# door_lock_2.net
KiCad netlist of a schematic drawn in EAGLE
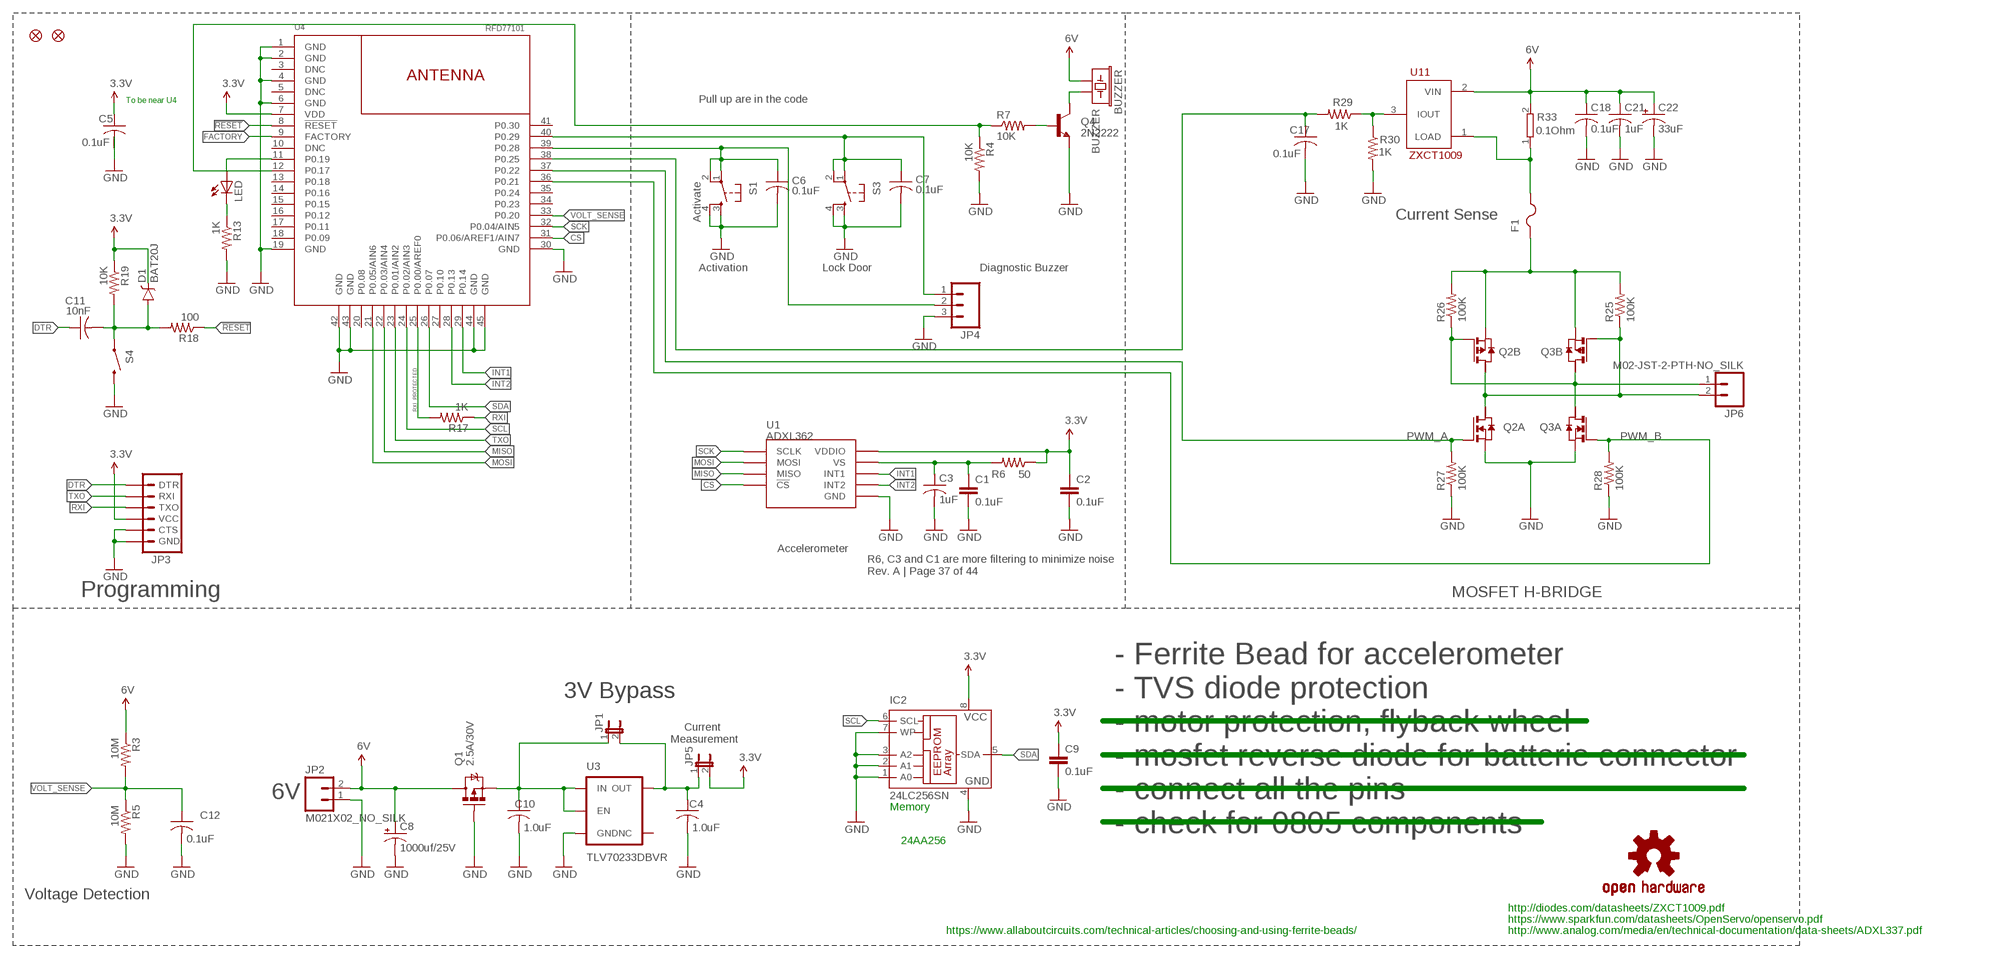
[diagram p0: schematic, sheet 1]

(export (version "E")
  (design (tool "Eeschema 10.0.6"))
  (components
    (comp (ref "BUZZER")
      (value "BUZZER")
      (footprint "eagle-import:BUZZER-12MM-NS")
      (libsource (lib "eagle-import") (part "BUZZERNS"))
    )
    (comp (ref "C1")
      (value "0.1uF")
      (footprint "eagle-import:0805")
      (libsource (lib "eagle-import") (part "CAP0805"))
    )
    (comp (ref "C2")
      (value "0.1uF")
      (footprint "eagle-import:0805")
      (libsource (lib "eagle-import") (part "CAP0805"))
    )
    (comp (ref "C3")
      (value "1uF")
      (footprint "eagle-import:C0805")
      (libsource (lib "eagle-import") (part "C-USC0805"))
    )
    (comp (ref "C4")
      (value "1.0uF")
      (footprint "eagle-import:C0805")
      (libsource (lib "eagle-import") (part "C-USC0805"))
    )
    (comp (ref "C5")
      (value "0.1uF")
      (footprint "eagle-import:C0805")
      (libsource (lib "eagle-import") (part "C-USC0805"))
    )
    (comp (ref "C6")
      (value "0.1uF")
      (footprint "eagle-import:C0805")
      (libsource (lib "eagle-import") (part "C-USC0805"))
    )
    (comp (ref "C7")
      (value "0.1uF")
      (footprint "eagle-import:C0805")
      (libsource (lib "eagle-import") (part "C-USC0805"))
    )
    (comp (ref "C8")
      (value "1000uf/25V")
      (footprint "eagle-import:CPOL-RADIAL-1000UF-25V-KIT")
      (libsource (lib "eagle-import") (part "1000UF-25V(PTH)KIT"))
    )
    (comp (ref "C9")
      (value "0.1uF")
      (footprint "eagle-import:0805")
      (libsource (lib "eagle-import") (part "CAP0805"))
    )
    (comp (ref "C10")
      (value "1.0uF")
      (footprint "eagle-import:C0805")
      (libsource (lib "eagle-import") (part "C-USC0805"))
    )
    (comp (ref "C11")
      (value "10nF")
      (footprint "eagle-import:C0805")
      (libsource (lib "eagle-import") (part "C-USC0805"))
    )
    (comp (ref "C12")
      (value "0.1uF")
      (footprint "eagle-import:C0805")
      (libsource (lib "eagle-import") (part "C-USC0805"))
    )
    (comp (ref "C17")
      (value "0.1uF")
      (footprint "eagle-import:C0805")
      (libsource (lib "eagle-import") (part "C-USC0805"))
    )
    (comp (ref "C18")
      (value "0.1uF")
      (footprint "eagle-import:C0805")
      (libsource (lib "eagle-import") (part "C-USC0805"))
    )
    (comp (ref "C21")
      (value "1uF")
      (footprint "eagle-import:C0805")
      (libsource (lib "eagle-import") (part "C-USC0805"))
    )
    (comp (ref "C22")
      (value "33uF")
      (footprint "eagle-import:EIA3528")
      (libsource (lib "eagle-import") (part "CAP_POL3528"))
    )
    (comp (ref "D1")
      (value "BAT20J")
      (footprint "eagle-import:SOD-323")
      (libsource (lib "eagle-import") (part "DIODE-SCHOTTKY-BAT20J"))
    )
    (comp (ref "F1")
      (value "PTCFUSE-1812")
      (footprint "eagle-import:1812")
      (libsource (lib "eagle-import") (part "PTCFUSE-1812"))
    )
    (comp (ref "IC2")
      (value "24LC256SN")
      (footprint "eagle-import:SO-08")
      (fields (field (name "MF") "MICROCHIP") (field (name "MPN") "24LC256-I/SN"))
      (libsource (lib "eagle-import") (part "24SNLC256"))
    )
    (comp (ref "JP1")
      (value "JUMPER-2SMD-NO")
      (footprint "eagle-import:SJ_2S-NO")
      (libsource (lib "eagle-import") (part "SparkFun-Retired_JUMPER-2SMD-NO"))
    )
    (comp (ref "JP2")
      (value "M021X02_NO_SILK")
      (footprint "eagle-import:1X02_NO_SILK")
      (libsource (lib "eagle-import") (part "M021X02_NO_SILK"))
    )
    (comp (ref "JP3")
      (value "ARDUINO_SERIAL_PROGRAMPTH")
      (footprint "eagle-import:1X06")
      (libsource (lib "eagle-import") (part "ARDUINO_SERIAL_PROGRAMPTH"))
    )
    (comp (ref "JP4")
      (value "M03PTH")
      (footprint "eagle-import:1X03")
      (libsource (lib "eagle-import") (part "M03PTH"))
    )
    (comp (ref "JP5")
      (value "JUMPER-2PTH")
      (footprint "eagle-import:1X02")
      (libsource (lib "eagle-import") (part "JUMPER-2PTH"))
    )
    (comp (ref "JP6")
      (value "M02-JST-2-PTH-NO_SILK")
      (footprint "eagle-import:JST-2-PTH-NS")
      (libsource (lib "eagle-import") (part "M02-JST-2-PTH-NO_SILK"))
    )
    (comp (ref "JP9")
      (value "FIDUCIALUFIDUCIAL")
      (footprint "eagle-import:MICRO-FIDUCIAL")
      (libsource (lib "eagle-import") (part "FIDUCIALUFIDUCIAL"))
    )
    (comp (ref "JP10")
      (value "FIDUCIALUFIDUCIAL")
      (footprint "eagle-import:MICRO-FIDUCIAL")
      (libsource (lib "eagle-import") (part "FIDUCIALUFIDUCIAL"))
    )
    (comp (ref "LED")
      (value "LEDCHIP-LED0805")
      (footprint "eagle-import:CHIP-LED0805")
      (libsource (lib "eagle-import") (part "LEDCHIP-LED0805"))
    )
    (comp (ref "Q1")
      (value "2.5A/30V")
      (footprint "eagle-import:SOT23-3")
      (libsource (lib "eagle-import") (part "MOSFET-PCHANNELDMG2307L"))
    )
    (comp (ref "Q2")
      (value "PN_MOSFET-SO8")
      (footprint "eagle-import:SO8")
      (libsource (lib "eagle-import") (part "PN_MOSFET-SO8"))
    )
    (comp (ref "Q3")
      (value "PN_MOSFET-SO8")
      (footprint "eagle-import:SO8")
      (libsource (lib "eagle-import") (part "PN_MOSFET-SO8"))
    )
    (comp (ref "Q4")
      (value "2N2222")
      (footprint "eagle-import:SOT23")
      (libsource (lib "eagle-import") (part "TRANSISTOR_NPNSOT23"))
    )
    (comp (ref "R3")
      (value "10M")
      (footprint "eagle-import:R0805")
      (libsource (lib "eagle-import") (part "R-US_R0805"))
    )
    (comp (ref "R4")
      (value "10K")
      (footprint "eagle-import:R0805")
      (libsource (lib "eagle-import") (part "R-US_R0805"))
    )
    (comp (ref "R5")
      (value "10M")
      (footprint "eagle-import:R0805")
      (libsource (lib "eagle-import") (part "R-US_R0805"))
    )
    (comp (ref "R6")
      (value "50")
      (footprint "eagle-import:R0805")
      (libsource (lib "eagle-import") (part "R-US_R0805"))
    )
    (comp (ref "R7")
      (value "10K")
      (footprint "eagle-import:R0805")
      (libsource (lib "eagle-import") (part "R-US_R0805"))
    )
    (comp (ref "R13")
      (value "1K")
      (footprint "eagle-import:R0805")
      (libsource (lib "eagle-import") (part "R-US_R0805"))
    )
    (comp (ref "R17")
      (value "1K")
      (footprint "eagle-import:R0805")
      (libsource (lib "eagle-import") (part "R-US_R0805"))
    )
    (comp (ref "R18")
      (value "100")
      (footprint "eagle-import:R0805")
      (libsource (lib "eagle-import") (part "R-US_R0805"))
    )
    (comp (ref "R19")
      (value "10K")
      (footprint "eagle-import:R0805")
      (libsource (lib "eagle-import") (part "R-US_R0805"))
    )
    (comp (ref "R25")
      (value "100K")
      (footprint "eagle-import:R0805")
      (libsource (lib "eagle-import") (part "R-US_R0805"))
    )
    (comp (ref "R26")
      (value "100K")
      (footprint "eagle-import:R0805")
      (libsource (lib "eagle-import") (part "R-US_R0805"))
    )
    (comp (ref "R27")
      (value "100K")
      (footprint "eagle-import:R0805")
      (libsource (lib "eagle-import") (part "R-US_R0805"))
    )
    (comp (ref "R28")
      (value "100K")
      (footprint "eagle-import:R0805")
      (libsource (lib "eagle-import") (part "R-US_R0805"))
    )
    (comp (ref "R29")
      (value "1K")
      (footprint "eagle-import:R0805")
      (libsource (lib "eagle-import") (part "R-US_R0805"))
    )
    (comp (ref "R30")
      (value "1K")
      (footprint "eagle-import:R0805")
      (libsource (lib "eagle-import") (part "R-US_R0805"))
    )
    (comp (ref "R33")
      (value "0.1Ohm")
      (footprint "eagle-import:R1206W")
      (libsource (lib "eagle-import") (part "R1206W"))
    )
    (comp (ref "S1")
      (value "Activate")
      (footprint "eagle-import:TACTILE-PTH")
      (libsource (lib "eagle-import") (part "TAC_SWITCHPTH"))
    )
    (comp (ref "S3")
      (value "TAC_SWITCHPTH")
      (footprint "eagle-import:TACTILE-PTH")
      (libsource (lib "eagle-import") (part "TAC_SWITCHPTH"))
    )
    (comp (ref "S4")
      (value "SWITCH-MOMENTARY-2SMD")
      (footprint "eagle-import:TACTILE-SWITCH-SMD")
      (libsource (lib "eagle-import") (part "SWITCH-MOMENTARY-2SMD"))
    )
    (comp (ref "U$3")
      (value "OSHW-LOGOS")
      (footprint "eagle-import:OSHW-LOGO-S")
      (libsource (lib "eagle-import") (part "OSHW-LOGOS"))
    )
    (comp (ref "U1")
      (value "ADXL362")
      (footprint "eagle-import:ADXL362")
      (libsource (lib "eagle-import") (part "ADXL362"))
    )
    (comp (ref "U3")
      (value "TLV70233DBVR")
      (footprint "eagle-import:SOT23-5")
      (libsource (lib "eagle-import") (part "V_REG_AP2112K-3.3V"))
    )
    (comp (ref "U4")
      (value "RFD77101")
      (footprint "eagle-import:RFD77101")
      (libsource (lib "eagle-import") (part "RFD77101"))
    )
    (comp (ref "U11")
      (value "ZXCT1009")
      (footprint "eagle-import:SOT23-3")
      (libsource (lib "eagle-import") (part "ZCT1009FTA"))
    )
  )
  (nets
    (net (code "2") (name "/PWM_A") (class "Default")
      (node (ref "Q2") (pin "2") (pinfunction "G_2") (pintype "passive"))
      (node (ref "R27") (pin "2") (pinfunction "2_2") (pintype "passive"))
      (node (ref "U4") (pin "37") (pinfunction "P0.22_37") (pintype "bidirectional"))
    )
    (net (code "3") (name "/PWM_B") (class "Default")
      (node (ref "Q3") (pin "2") (pinfunction "G_2") (pintype "passive"))
      (node (ref "R28") (pin "2") (pinfunction "2_2") (pintype "passive"))
      (node (ref "U4") (pin "36") (pinfunction "P0.21_36") (pintype "bidirectional"))
    )
    (net (code "4") (name "/RXI_PROTECTED") (class "Default")
      (node (ref "R17") (pin "2") (pinfunction "2_2") (pintype "passive"))
      (node (ref "U4") (pin "25") (pinfunction "P0.00/AREF0_25") (pintype "bidirectional"))
    )
    (net (code "5") (name "/~{RESET}") (class "Default")
      (node (ref "R18") (pin "1") (pinfunction "1_1") (pintype "passive"))
      (node (ref "U4") (pin "8") (pinfunction "~{RESET}_8") (pintype "input"))
    )
    (net (code "6") (name "3.3V") (class "Default")
      (node (ref "C2") (pin "1") (pinfunction "1_1") (pintype "passive"))
      (node (ref "C5") (pin "1") (pinfunction "1_1") (pintype "passive"))
      (node (ref "C9") (pin "1") (pinfunction "1_1") (pintype "passive"))
      (node (ref "D1") (pin "C") (pinfunction "C_C") (pintype "passive"))
      (node (ref "IC2") (pin "8") (pinfunction "VCC_8") (pintype "power_in"))
      (node (ref "JP3") (pin "4") (pinfunction "VCC_4") (pintype "passive"))
      (node (ref "JP5") (pin "2") (pinfunction "2_2") (pintype "passive"))
      (node (ref "R19") (pin "1") (pinfunction "1_1") (pintype "passive"))
      (node (ref "R6") (pin "1") (pinfunction "1_1") (pintype "passive"))
      (node (ref "U1") (pin "P$1") (pinfunction "VDDIO_P$1") (pintype "bidirectional"))
      (node (ref "U4") (pin "7") (pinfunction "VDD_7") (pintype "power_in"))
    )
    (net (code "7") (name "6V") (class "Default")
      (node (ref "BUZZER") (pin "+") (pinfunction "1_+") (pintype "passive"))
      (node (ref "C18") (pin "1") (pinfunction "1_1") (pintype "passive"))
      (node (ref "C21") (pin "1") (pinfunction "1_1") (pintype "passive"))
      (node (ref "C22") (pin "A") (pinfunction "+_A") (pintype "passive"))
      (node (ref "C8") (pin "+") (pinfunction "+_+") (pintype "passive"))
      (node (ref "JP2") (pin "2") (pinfunction "2_2") (pintype "passive"))
      (node (ref "Q1") (pin "3") (pinfunction "D_3") (pintype "passive"))
      (node (ref "R3") (pin "1") (pinfunction "1_1") (pintype "passive"))
      (node (ref "R33") (pin "2") (pinfunction "2_2") (pintype "passive"))
      (node (ref "U11") (pin "2") (pinfunction "VIN_2") (pintype "bidirectional"))
    )
    (net (code "8") (name "CS") (class "Default")
      (node (ref "U1") (pin "P$8") (pinfunction "~{CS}_P$8") (pintype "bidirectional"))
      (node (ref "U4") (pin "31") (pinfunction "P0.06/AREF1/AIN7_31") (pintype "bidirectional"))
    )
    (net (code "9") (name "DTR") (class "Default")
      (node (ref "C11") (pin "1") (pinfunction "1_1") (pintype "passive"))
      (node (ref "JP3") (pin "1") (pinfunction "DTR_1") (pintype "passive"))
    )
    (net (code "11") (name "FACTORY") (class "Default")
      (node (ref "U4") (pin "9") (pinfunction "FACTORY_9") (pintype "no_connect"))
    )
    (net (code "12") (name "GND") (class "Default")
      (node (ref "C1") (pin "2") (pinfunction "2_2") (pintype "passive"))
      (node (ref "C10") (pin "2") (pinfunction "2_2") (pintype "passive"))
      (node (ref "C12") (pin "2") (pinfunction "2_2") (pintype "passive"))
      (node (ref "C17") (pin "2") (pinfunction "2_2") (pintype "passive"))
      (node (ref "C18") (pin "2") (pinfunction "2_2") (pintype "passive"))
      (node (ref "C2") (pin "2") (pinfunction "2_2") (pintype "passive"))
      (node (ref "C21") (pin "2") (pinfunction "2_2") (pintype "passive"))
      (node (ref "C22") (pin "C") (pinfunction "-_C") (pintype "passive"))
      (node (ref "C3") (pin "2") (pinfunction "2_2") (pintype "passive"))
      (node (ref "C4") (pin "2") (pinfunction "2_2") (pintype "passive"))
      (node (ref "C5") (pin "2") (pinfunction "2_2") (pintype "passive"))
      (node (ref "C6") (pin "2") (pinfunction "2_2") (pintype "passive"))
      (node (ref "C7") (pin "2") (pinfunction "2_2") (pintype "passive"))
      (node (ref "C8") (pin "-") (pinfunction "-_-") (pintype "passive"))
      (node (ref "C9") (pin "2") (pinfunction "2_2") (pintype "passive"))
      (node (ref "IC2") (pin "1") (pinfunction "A0_1") (pintype "input"))
      (node (ref "IC2") (pin "2") (pinfunction "A1_2") (pintype "input"))
      (node (ref "IC2") (pin "3") (pinfunction "A2_3") (pintype "input"))
      (node (ref "IC2") (pin "4") (pinfunction "GND_4") (pintype "power_in"))
      (node (ref "IC2") (pin "7") (pinfunction "WP_7") (pintype "input"))
      (node (ref "JP2") (pin "1") (pinfunction "1_1") (pintype "passive"))
      (node (ref "JP3") (pin "5") (pinfunction "CTS_5") (pintype "passive"))
      (node (ref "JP3") (pin "6") (pinfunction "GND_6") (pintype "passive"))
      (node (ref "JP4") (pin "3") (pinfunction "3_3") (pintype "passive"))
      (node (ref "Q1") (pin "1") (pinfunction "G_1") (pintype "passive"))
      (node (ref "Q2") (pin "1") (pinfunction "S_1") (pintype "passive"))
      (node (ref "Q3") (pin "1") (pinfunction "S_1") (pintype "passive"))
      (node (ref "Q4") (pin "2") (pinfunction "E_2") (pintype "passive"))
      (node (ref "R13") (pin "2") (pinfunction "2_2") (pintype "passive"))
      (node (ref "R27") (pin "1") (pinfunction "1_1") (pintype "passive"))
      (node (ref "R28") (pin "1") (pinfunction "1_1") (pintype "passive"))
      (node (ref "R30") (pin "2") (pinfunction "2_2") (pintype "passive"))
      (node (ref "R4") (pin "2") (pinfunction "2_2") (pintype "passive"))
      (node (ref "R5") (pin "2") (pinfunction "2_2") (pintype "passive"))
      (node (ref "S1") (pin "3") (pinfunction "3_3") (pintype "passive"))
      (node (ref "S1") (pin "4") (pinfunction "4_4") (pintype "passive"))
      (node (ref "S3") (pin "3") (pinfunction "3_3") (pintype "passive"))
      (node (ref "S3") (pin "4") (pinfunction "4_4") (pintype "passive"))
      (node (ref "S4") (pin "3") (pinfunction "2_3") (pintype "passive"))
      (node (ref "U1") (pin "P$12") (pinfunction "GND_P$12") (pintype "bidirectional"))
      (node (ref "U1") (pin "P$13") (pinfunction "GND_P$13") (pintype "bidirectional"))
      (node (ref "U1") (pin "P$16") (pinfunction "GND_P$16") (pintype "bidirectional"))
      (node (ref "U3") (pin "2") (pinfunction "GND_2") (pintype "input"))
      (node (ref "U4") (pin "1") (pinfunction "GND_1") (pintype "power_in"))
      (node (ref "U4") (pin "19") (pinfunction "GND_19") (pintype "power_in"))
      (node (ref "U4") (pin "2") (pinfunction "GND_2") (pintype "power_in"))
      (node (ref "U4") (pin "30") (pinfunction "GND_30") (pintype "power_in"))
      (node (ref "U4") (pin "4") (pinfunction "GND_4") (pintype "power_in"))
      (node (ref "U4") (pin "42") (pinfunction "GND_42") (pintype "power_in"))
      (node (ref "U4") (pin "43") (pinfunction "GND_43") (pintype "power_in"))
      (node (ref "U4") (pin "44") (pinfunction "GND_44") (pintype "power_in"))
      (node (ref "U4") (pin "45") (pinfunction "GND_45") (pintype "power_in"))
      (node (ref "U4") (pin "6") (pinfunction "GND_6") (pintype "power_in"))
    )
    (net (code "13") (name "INT1") (class "Default")
      (node (ref "U1") (pin "P$11") (pinfunction "INT1_P$11") (pintype "bidirectional"))
      (node (ref "U4") (pin "29") (pinfunction "P0.14_29") (pintype "bidirectional"))
    )
    (net (code "14") (name "INT2") (class "Default")
      (node (ref "U1") (pin "P$9") (pinfunction "INT2_P$9") (pintype "bidirectional"))
      (node (ref "U4") (pin "28") (pinfunction "P0.13_28") (pintype "bidirectional"))
    )
    (net (code "15") (name "MISO") (class "Default")
      (node (ref "U1") (pin "P$7") (pinfunction "MISO_P$7") (pintype "bidirectional"))
      (node (ref "U4") (pin "22") (pinfunction "P0.03/AIN4_22") (pintype "bidirectional"))
    )
    (net (code "16") (name "MOSI") (class "Default")
      (node (ref "U1") (pin "P$6") (pinfunction "MOSI_P$6") (pintype "bidirectional"))
      (node (ref "U4") (pin "21") (pinfunction "P0.05/AIN6_21") (pintype "bidirectional"))
    )
    (net (code "17") (name "Net-(BUZZER-2)") (class "Default")
      (node (ref "BUZZER") (pin "-") (pinfunction "2_-") (pintype "passive"))
      (node (ref "Q4") (pin "3") (pinfunction "C_3") (pintype "passive"))
    )
    (net (code "18") (name "Net-(C11-Pad2)") (class "Default")
      (node (ref "C11") (pin "2") (pinfunction "2_2") (pintype "passive"))
      (node (ref "D1") (pin "A") (pinfunction "A_A") (pintype "passive"))
      (node (ref "R18") (pin "2") (pinfunction "2_2") (pintype "passive"))
      (node (ref "R19") (pin "2") (pinfunction "2_2") (pintype "passive"))
      (node (ref "S4") (pin "1") (pinfunction "1_1") (pintype "passive"))
    )
    (net (code "19") (name "Net-(LED-PadC)") (class "Default")
      (node (ref "LED") (pin "C") (pinfunction "C_C") (pintype "passive"))
      (node (ref "R13") (pin "1") (pinfunction "1_1") (pintype "passive"))
    )
    (net (code "20") (name "Net-(Q1-S)") (class "Default")
      (node (ref "C10") (pin "1") (pinfunction "1_1") (pintype "passive"))
      (node (ref "JP1") (pin "1") (pinfunction "1_1") (pintype "passive"))
      (node (ref "Q1") (pin "2") (pinfunction "S_2") (pintype "passive"))
      (node (ref "U3") (pin "1") (pinfunction "IN_1") (pintype "input"))
      (node (ref "U3") (pin "3") (pinfunction "EN_3") (pintype "input"))
    )
    (net (code "21") (name "Net-(Q2A-D)") (class "Default")
      (node (ref "JP6") (pin "2") (pinfunction "2_2") (pintype "passive"))
      (node (ref "Q2") (pin "5") (pinfunction "D_5") (pintype "passive"))
      (node (ref "Q2") (pin "7") (pinfunction "D_7") (pintype "passive"))
      (node (ref "Q3") (pin "4") (pinfunction "G_4") (pintype "passive"))
      (node (ref "R25") (pin "1") (pinfunction "1_1") (pintype "passive"))
    )
    (net (code "22") (name "Net-(Q2B-G)") (class "Default")
      (node (ref "JP6") (pin "1") (pinfunction "1_1") (pintype "passive"))
      (node (ref "Q2") (pin "4") (pinfunction "G_4") (pintype "passive"))
      (node (ref "Q3") (pin "5") (pinfunction "D_5") (pintype "passive"))
      (node (ref "Q3") (pin "7") (pinfunction "D_7") (pintype "passive"))
      (node (ref "R26") (pin "1") (pinfunction "1_1") (pintype "passive"))
    )
    (net (code "23") (name "Net-(Q2B-S)") (class "Default")
      (node (ref "F1") (pin "1") (pinfunction "1_1") (pintype "passive"))
      (node (ref "Q2") (pin "3") (pinfunction "S_3") (pintype "passive"))
      (node (ref "Q3") (pin "3") (pinfunction "S_3") (pintype "passive"))
      (node (ref "R25") (pin "2") (pinfunction "2_2") (pintype "passive"))
      (node (ref "R26") (pin "2") (pinfunction "2_2") (pintype "passive"))
    )
    (net (code "24") (name "Net-(Q4-B)") (class "Default")
      (node (ref "Q4") (pin "1") (pinfunction "B_1") (pintype "passive"))
      (node (ref "R7") (pin "2") (pinfunction "2_2") (pintype "passive"))
    )
    (net (code "25") (name "Net-(U1-VS)") (class "Default")
      (node (ref "C1") (pin "1") (pinfunction "1_1") (pintype "passive"))
      (node (ref "C3") (pin "1") (pinfunction "1_1") (pintype "passive"))
      (node (ref "R6") (pin "2") (pinfunction "2_2") (pintype "passive"))
      (node (ref "U1") (pin "P$14") (pinfunction "VS_P$14") (pintype "bidirectional"))
    )
    (net (code "26") (name "Net-(U3-OUT)") (class "Default")
      (node (ref "C4") (pin "1") (pinfunction "1_1") (pintype "passive"))
      (node (ref "JP1") (pin "2") (pinfunction "2_2") (pintype "passive"))
      (node (ref "JP5") (pin "1") (pinfunction "1_1") (pintype "passive"))
      (node (ref "U3") (pin "5") (pinfunction "OUT_5") (pintype "passive"))
    )
    (net (code "27") (name "Net-(U4-P0.17)") (class "Default")
      (node (ref "R4") (pin "1") (pinfunction "1_1") (pintype "passive"))
      (node (ref "R7") (pin "1") (pinfunction "1_1") (pintype "passive"))
      (node (ref "U4") (pin "12") (pinfunction "P0.17_12") (pintype "bidirectional"))
    )
    (net (code "28") (name "Net-(U4-P0.19)") (class "Default")
      (node (ref "LED") (pin "A") (pinfunction "A_A") (pintype "passive"))
      (node (ref "U4") (pin "11") (pinfunction "P0.19_11") (pintype "bidirectional"))
    )
    (net (code "29") (name "Net-(U4-P0.25)") (class "Default")
      (node (ref "C17") (pin "1") (pinfunction "1_1") (pintype "passive"))
      (node (ref "R29") (pin "2") (pinfunction "2_2") (pintype "passive"))
      (node (ref "U4") (pin "38") (pinfunction "P0.25_38") (pintype "bidirectional"))
    )
    (net (code "30") (name "Net-(U4-P0.28)") (class "Default")
      (node (ref "C6") (pin "1") (pinfunction "1_1") (pintype "passive"))
      (node (ref "JP4") (pin "2") (pinfunction "2_2") (pintype "passive"))
      (node (ref "S1") (pin "1") (pinfunction "1_1") (pintype "passive"))
      (node (ref "S1") (pin "2") (pinfunction "2_2") (pintype "passive"))
      (node (ref "U4") (pin "39") (pinfunction "P0.28_39") (pintype "bidirectional"))
    )
    (net (code "31") (name "Net-(U4-P0.29)") (class "Default")
      (node (ref "C7") (pin "1") (pinfunction "1_1") (pintype "passive"))
      (node (ref "JP4") (pin "1") (pinfunction "1_1") (pintype "passive"))
      (node (ref "S3") (pin "1") (pinfunction "1_1") (pintype "passive"))
      (node (ref "S3") (pin "2") (pinfunction "2_2") (pintype "passive"))
      (node (ref "U4") (pin "40") (pinfunction "P0.29_40") (pintype "bidirectional"))
    )
    (net (code "32") (name "Net-(U11-IOUT)") (class "Default")
      (node (ref "R29") (pin "1") (pinfunction "1_1") (pintype "passive"))
      (node (ref "R30") (pin "1") (pinfunction "1_1") (pintype "passive"))
      (node (ref "U11") (pin "3") (pinfunction "IOUT_3") (pintype "bidirectional"))
    )
    (net (code "33") (name "Net-(U11-LOAD)") (class "Default")
      (node (ref "F1") (pin "2") (pinfunction "2_2") (pintype "passive"))
      (node (ref "R33") (pin "1") (pinfunction "1_1") (pintype "passive"))
      (node (ref "U11") (pin "1") (pinfunction "LOAD_1") (pintype "bidirectional"))
    )
    (net (code "34") (name "RXI") (class "Default")
      (node (ref "JP3") (pin "3") (pinfunction "TXO_3") (pintype "passive"))
      (node (ref "R17") (pin "1") (pinfunction "1_1") (pintype "passive"))
    )
    (net (code "35") (name "SCK") (class "Default")
      (node (ref "U1") (pin "P$4") (pinfunction "SCLK_P$4") (pintype "bidirectional"))
      (node (ref "U4") (pin "32") (pinfunction "P0.04/AIN5_32") (pintype "bidirectional"))
    )
    (net (code "36") (name "SCL") (class "Default")
      (node (ref "IC2") (pin "6") (pinfunction "SCL_6") (pintype "input"))
      (node (ref "U4") (pin "24") (pinfunction "P0.02/AIN3_24") (pintype "bidirectional"))
    )
    (net (code "37") (name "SDA") (class "Default")
      (node (ref "IC2") (pin "5") (pinfunction "SDA_5") (pintype "bidirectional"))
      (node (ref "U4") (pin "26") (pinfunction "P0.07_26") (pintype "bidirectional"))
    )
    (net (code "38") (name "TXO") (class "Default")
      (node (ref "JP3") (pin "2") (pinfunction "RXI_2") (pintype "passive"))
      (node (ref "U4") (pin "23") (pinfunction "P0.01/AIN2_23") (pintype "bidirectional"))
    )
    (net (code "39") (name "VOLT_SENSE") (class "Default")
      (node (ref "C12") (pin "1") (pinfunction "1_1") (pintype "passive"))
      (node (ref "R3") (pin "2") (pinfunction "2_2") (pintype "passive"))
      (node (ref "R5") (pin "1") (pinfunction "1_1") (pintype "passive"))
      (node (ref "U4") (pin "33") (pinfunction "P0.20_33") (pintype "bidirectional"))
    )
    (net (code "40") (name "unconnected-(Q2A-D2-Pad8)") (class "Default")
      (node (ref "Q2") (pin "8") (pinfunction "D2_8") (pintype "passive"))
    )
    (net (code "41") (name "unconnected-(Q2B-D2-Pad6)") (class "Default")
      (node (ref "Q2") (pin "6") (pinfunction "D2_6") (pintype "passive"))
    )
    (net (code "42") (name "unconnected-(Q3A-D2-Pad8)") (class "Default")
      (node (ref "Q3") (pin "8") (pinfunction "D2_8") (pintype "passive"))
    )
    (net (code "43") (name "unconnected-(Q3B-D2-Pad6)") (class "Default")
      (node (ref "Q3") (pin "6") (pinfunction "D2_6") (pintype "passive"))
    )
    (net (code "44") (name "unconnected-(U3-NC-Pad4)") (class "Default")
      (node (ref "U3") (pin "4") (pinfunction "NC_4") (pintype "input"))
    )
    (net (code "45") (name "unconnected-(U4-DNC-Pad3)") (class "Default")
      (node (ref "U4") (pin "3") (pinfunction "DNC_3") (pintype "no_connect"))
    )
    (net (code "46") (name "unconnected-(U4-DNC-Pad5)") (class "Default")
      (node (ref "U4") (pin "5") (pinfunction "DNC_5") (pintype "no_connect"))
    )
    (net (code "47") (name "unconnected-(U4-DNC-Pad10)") (class "Default")
      (node (ref "U4") (pin "10") (pinfunction "DNC_10") (pintype "no_connect"))
    )
    (net (code "48") (name "unconnected-(U4-P0.08-Pad20)") (class "Default")
      (node (ref "U4") (pin "20") (pinfunction "P0.08_20") (pintype "bidirectional"))
    )
    (net (code "49") (name "unconnected-(U4-P0.09-Pad18)") (class "Default")
      (node (ref "U4") (pin "18") (pinfunction "P0.09_18") (pintype "bidirectional"))
    )
    (net (code "50") (name "unconnected-(U4-P0.10-Pad27)") (class "Default")
      (node (ref "U4") (pin "27") (pinfunction "P0.10_27") (pintype "bidirectional"))
    )
    (net (code "51") (name "unconnected-(U4-P0.11-Pad17)") (class "Default")
      (node (ref "U4") (pin "17") (pinfunction "P0.11_17") (pintype "bidirectional"))
    )
    (net (code "52") (name "unconnected-(U4-P0.12-Pad16)") (class "Default")
      (node (ref "U4") (pin "16") (pinfunction "P0.12_16") (pintype "bidirectional"))
    )
    (net (code "53") (name "unconnected-(U4-P0.15-Pad15)") (class "Default")
      (node (ref "U4") (pin "15") (pinfunction "P0.15_15") (pintype "bidirectional"))
    )
    (net (code "54") (name "unconnected-(U4-P0.16-Pad14)") (class "Default")
      (node (ref "U4") (pin "14") (pinfunction "P0.16_14") (pintype "bidirectional"))
    )
    (net (code "55") (name "unconnected-(U4-P0.18-Pad13)") (class "Default")
      (node (ref "U4") (pin "13") (pinfunction "P0.18_13") (pintype "bidirectional"))
    )
    (net (code "56") (name "unconnected-(U4-P0.23-Pad34)") (class "Default")
      (node (ref "U4") (pin "34") (pinfunction "P0.23_34") (pintype "bidirectional"))
    )
    (net (code "57") (name "unconnected-(U4-P0.24-Pad35)") (class "Default")
      (node (ref "U4") (pin "35") (pinfunction "P0.24_35") (pintype "bidirectional"))
    )
    (net (code "58") (name "unconnected-(U4-P0.30-Pad41)") (class "Default")
      (node (ref "U4") (pin "41") (pinfunction "P0.30_41") (pintype "bidirectional"))
    )
  )
)
